# PD_MK2_Connectors.net
KiCad netlist of a schematic drawn in Altium Designer
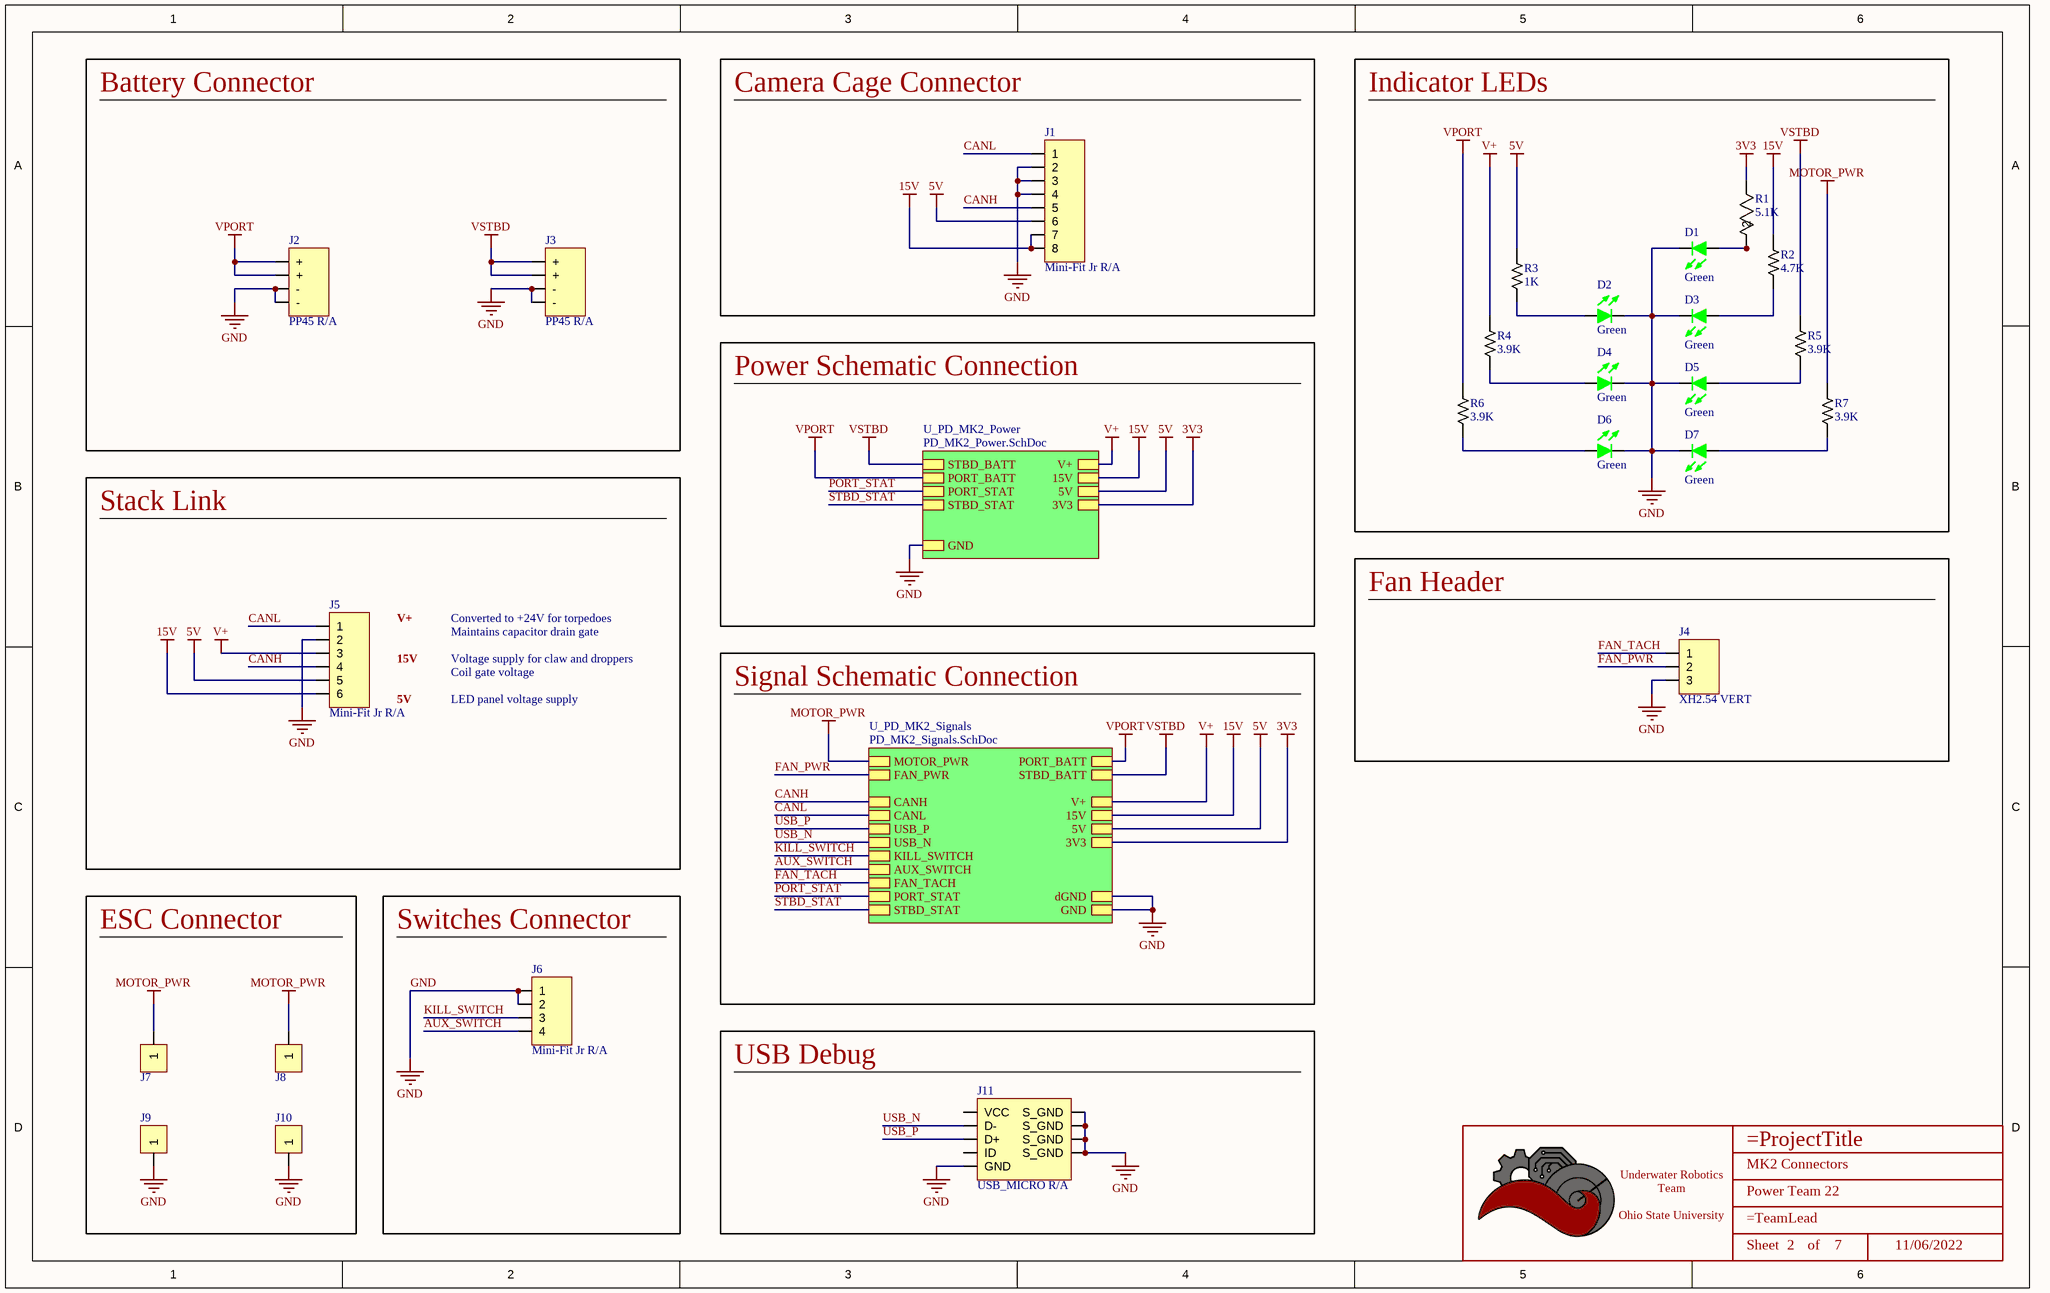
[diagram p0: PD_MK2_Connectors.SchDoc]

(export (version "E")
  (design (tool "Eeschema 10.0.6"))
  (components
    (comp (ref "*")
      (value "Title_Block")
      (footprint "LOGO")
      (description "UWRT Schematic Title Block Template\r\n\r\nCreated June 2021, Dylan Trainor")
      (libsource (lib "UWRT") (part "Title_Block"))
    )
    (comp (ref "D1")
      (value "IN-S63AT5G")
      (footprint "LED_0603")
      (description "LED Green Vf= 3V If = 0.005A\r\nIN-S63AT5G")
      (fields (field (name "COLOR") "Green") (field (name "MADE BY") "Robert Pafford"))
      (libsource (lib "Diodes") (part "LED_Green_0603_3V"))
    )
    (comp (ref "D2")
      (value "IN-S63AT5G")
      (footprint "LED_0603")
      (description "LED Green Vf= 3V If = 0.005A\r\nIN-S63AT5G")
      (fields (field (name "COLOR") "Green") (field (name "MADE BY") "Robert Pafford"))
      (libsource (lib "Diodes") (part "LED_Green_0603_3V"))
    )
    (comp (ref "D3")
      (value "IN-S63AT5G")
      (footprint "LED_0603")
      (description "LED Green Vf= 3V If = 0.005A\r\nIN-S63AT5G")
      (fields (field (name "COLOR") "Green") (field (name "MADE BY") "Robert Pafford"))
      (libsource (lib "Diodes") (part "LED_Green_0603_3V"))
    )
    (comp (ref "D4")
      (value "IN-S63AT5G")
      (footprint "LED_0603")
      (description "LED Green Vf= 3V If = 0.005A\r\nIN-S63AT5G")
      (fields (field (name "COLOR") "Green") (field (name "MADE BY") "Robert Pafford"))
      (libsource (lib "Diodes") (part "LED_Green_0603_3V"))
    )
    (comp (ref "D5")
      (value "IN-S63AT5G")
      (footprint "LED_0603")
      (description "LED Green Vf= 3V If = 0.005A\r\nIN-S63AT5G")
      (fields (field (name "COLOR") "Green") (field (name "MADE BY") "Robert Pafford"))
      (libsource (lib "Diodes") (part "LED_Green_0603_3V"))
    )
    (comp (ref "D6")
      (value "IN-S63AT5G")
      (footprint "LED_0603")
      (description "LED Green Vf= 3V If = 0.005A\r\nIN-S63AT5G")
      (fields (field (name "COLOR") "Green") (field (name "MADE BY") "Robert Pafford"))
      (libsource (lib "Diodes") (part "LED_Green_0603_3V"))
    )
    (comp (ref "D7")
      (value "IN-S63AT5G")
      (footprint "LED_0603")
      (description "LED Green Vf= 3V If = 0.005A\r\nIN-S63AT5G")
      (fields (field (name "COLOR") "Green") (field (name "MADE BY") "Robert Pafford"))
      (libsource (lib "Diodes") (part "LED_Green_0603_3V"))
    )
    (comp (ref "J1")
      (value "Mini-Fit Jr R/A")
      (footprint "CONN_MOLEX_MINIFIT JR_8 POS_R/A")
      (description "Molex Minifit Jr. 5569 \r\n8 Pos R/A Natural")
      (fields (field (name "MANUFACTURER") "Molex") (field (name "CREATED BY") "Flip B"))
      (libsource (lib "Connectors") (part "CONN_MOLEX_MINIFIT JR_8POS_R/A"))
    )
    (comp (ref "J2")
      (value "PP45 R/A")
      (footprint "CONN_ANDERSON_PP45_4 POS_R/A")
      (description "Anderson PP45\r\n4 Pos R/A Red/Black")
      (fields (field (name "MANUFACTURER") "Anderson") (field (name "CREATED BY") "Flip B"))
      (libsource (lib "Connectors") (part "CONN_ANDERSON_2x2_R/A"))
    )
    (comp (ref "J3")
      (value "PP45 R/A")
      (footprint "CONN_ANDERSON_PP45_4 POS_R/A")
      (description "Anderson PP45\r\n4 Pos R/A Red/Black")
      (fields (field (name "MANUFACTURER") "Anderson") (field (name "CREATED BY") "Flip B"))
      (libsource (lib "Connectors") (part "CONN_ANDERSON_2x2_R/A"))
    )
    (comp (ref "J4")
      (value "XH2.54 VERT")
      (footprint "CONN_JST_XH254_3POS_VERT")
      (description "JST XH 2.54mm Pitch 3 Pos Vertical")
      (fields (field (name "MANUFACTURER") "JST") (field (name "CREATED BY") "Robert P"))
      (libsource (lib "Connectors") (part "CONN_JST_XH254_3POS_VERT"))
    )
    (comp (ref "J5")
      (value "Mini-Fit Jr R/A")
      (footprint "CONN_MOLEX_MINIFIT JR_6 POS_R/A")
      (description "Molex Minifit Jr. 5569 \r\n6 Pos R/A Natural")
      (fields (field (name "MANUFACTURER") "Molex") (field (name "CREATED BY") "Flip B"))
      (libsource (lib "Connectors") (part "CONN_MOLEX_MINIFIT JR_6POS_R/A"))
    )
    (comp (ref "J6")
      (value "Mini-Fit Jr R/A")
      (footprint "CONN_MOLEX_MINIFIT JR_4 POS_R/A")
      (description "Molex Minifit Jr. 5569 \r\n4 Pos R/A Natural")
      (fields (field (name "MANUFACTURER") "Molex") (field (name "CREATED BY") "Flip B"))
      (libsource (lib "Connectors") (part "CONN_MOLEX_MINIFIT JR_4POS_R/A"))
    )
    (comp (ref "J7")
      (value "Redcube M4 Term 85A")
      (footprint "Redcube M4 Term 85A")
      (fields (field (name "CREATED BY") "Nahtan Ayer"))
      (libsource (lib "") (part "Redcube M4 Term 85A_1"))
    )
    (comp (ref "J8")
      (value "Redcube M4 Term 85A")
      (footprint "Redcube M4 Term 85A")
      (fields (field (name "CREATED BY") "Nahtan Ayer"))
      (libsource (lib "") (part "Redcube M4 Term 85A_1"))
    )
    (comp (ref "J9")
      (value "Redcube M4 Term 85A")
      (footprint "Redcube M4 Term 85A")
      (fields (field (name "CREATED BY") "Nahtan Ayer"))
      (libsource (lib "Connectors") (part "Redcube M4 Term 85A"))
    )
    (comp (ref "J10")
      (value "Redcube M4 Term 85A")
      (footprint "Redcube M4 Term 85A")
      (fields (field (name "CREATED BY") "Nahtan Ayer"))
      (libsource (lib "Connectors") (part "Redcube M4 Term 85A"))
    )
    (comp (ref "J11")
      (value "USB_MICRO R/A")
      (footprint "CONN_MINIUSB")
      (description "Amphenol Micro USB-B\r\nUSB2.0 5 Pin Right Angle SMD")
      (fields (field (name "MANUFACTURER") "Amphenol") (field (name "CREATED BY") "Flip B"))
      (libsource (lib "Connectors") (part "CONN_MICROUSB"))
    )
    (comp (ref "R1")
      (value "5.1K")
      (footprint "RC0603N_PAN")
      (description "5.1 kOhms ±0.1% 0.1W, 1/10W Chip Resistor 0603 (1608 Metric) Automotive AEC-Q200 Thin Film")
      (fields
        (field (name "MANUFACTURER_PART_NUMBER") "ERA-3AEB512V_2")
        (field (name "COPYRIGHT") "Copyright (C) 2023 Ultra Librarian. All rights reserved.")
      )
      (libsource (lib "Resistors") (part "ERA-3AEB512V_2"))
    )
    (comp (ref "R2")
      (value "4.7k Ohm 5% 1/10W")
      (footprint "RESISTOR_0603")
      (description "RES 4.7k OHM 5% 1/10W 0603")
      (fields
        (field (name "TOLERANCE") "+/- 5%")
        (field (name "VALUE  (OHMS)") "4.7K")
        (field (name "MADE BY") "Robert Pafford")
      )
      (libsource (lib "Resistors") (part "RESISTOR_4.7K_0603"))
    )
    (comp (ref "R3")
      (value "1k Ohm 5% 1/8W")
      (footprint "RESISTOR_0603")
      (description "RES 1k OHM 5% 1/8W 0603")
      (fields
        (field (name "TOLERANCE") "+/- 5%")
        (field (name "VALUE  (OHMS)") "1K")
        (field (name "MADE BY") "Robert Pafford")
      )
      (libsource (lib "Resistors") (part "RESISTOR_1K_0603"))
    )
    (comp (ref "R4")
      (value "3.9k Ohm 5% 1/10W")
      (footprint "RESISTOR_0603")
      (description "RES 3.9k OHM 1% 1/10W 0603")
      (fields
        (field (name "TOLERANCE") "+/- 1%")
        (field (name "VALUE  (OHMS)") "3.9K")
        (field (name "MADE BY") "Robert Pafford")
      )
      (libsource (lib "Resistors") (part "RESISTOR_3.9K_0603"))
    )
    (comp (ref "R5")
      (value "3.9k Ohm 5% 1/10W")
      (footprint "RESISTOR_0603")
      (description "RES 3.9k OHM 1% 1/10W 0603")
      (fields
        (field (name "TOLERANCE") "+/- 1%")
        (field (name "VALUE  (OHMS)") "3.9K")
        (field (name "MADE BY") "Robert Pafford")
      )
      (libsource (lib "Resistors") (part "RESISTOR_3.9K_0603"))
    )
    (comp (ref "R6")
      (value "3.9k Ohm 5% 1/10W")
      (footprint "RESISTOR_0603")
      (description "RES 3.9k OHM 1% 1/10W 0603")
      (fields
        (field (name "TOLERANCE") "+/- 1%")
        (field (name "VALUE  (OHMS)") "3.9K")
        (field (name "MADE BY") "Robert Pafford")
      )
      (libsource (lib "Resistors") (part "RESISTOR_3.9K_0603"))
    )
    (comp (ref "R7")
      (value "3.9k Ohm 5% 1/10W")
      (footprint "RESISTOR_0603")
      (description "RES 3.9k OHM 1% 1/10W 0603")
      (fields
        (field (name "TOLERANCE") "+/- 1%")
        (field (name "VALUE  (OHMS)") "3.9K")
        (field (name "MADE BY") "Robert Pafford")
      )
      (libsource (lib "Resistors") (part "RESISTOR_3.9K_0603"))
    )
  )
  (nets
    (net (code "1") (name "/AUX_SWITCH") (class "Default")
      (node (ref "J6") (pin "4") (pinfunction "4_4") (pintype "passive"))
    )
    (net (code "2") (name "/CANH") (class "Default")
      (node (ref "J1") (pin "5") (pinfunction "5_5") (pintype "passive"))
      (node (ref "J5") (pin "4") (pinfunction "4_4") (pintype "passive"))
    )
    (net (code "3") (name "/CANL") (class "Default")
      (node (ref "J1") (pin "1") (pinfunction "1_1") (pintype "passive"))
      (node (ref "J5") (pin "1") (pinfunction "1_1") (pintype "passive"))
    )
    (net (code "4") (name "/FAN_PWR") (class "Default")
      (node (ref "J4") (pin "2") (pinfunction "2_2") (pintype "passive"))
    )
    (net (code "5") (name "/FAN_TACH") (class "Default")
      (node (ref "J4") (pin "1") (pinfunction "1_1") (pintype "passive"))
    )
    (net (code "6") (name "/KILL_SWITCH") (class "Default")
      (node (ref "J6") (pin "3") (pinfunction "3_3") (pintype "passive"))
    )
    (net (code "9") (name "/USB_N") (class "Default")
      (node (ref "J11") (pin "2") (pinfunction "D-_2") (pintype "passive"))
    )
    (net (code "10") (name "/USB_P") (class "Default")
      (node (ref "J11") (pin "3") (pinfunction "D+_3") (pintype "passive"))
    )
    (net (code "11") (name "3V3") (class "Default")
      (node (ref "R1") (pin "1") (pinfunction "1_1") (pintype "passive"))
    )
    (net (code "12") (name "5V") (class "Default")
      (node (ref "J1") (pin "6") (pinfunction "6_6") (pintype "passive"))
      (node (ref "J5") (pin "5") (pinfunction "5_5") (pintype "passive"))
      (node (ref "R3") (pin "1") (pinfunction "1_1") (pintype "passive"))
    )
    (net (code "13") (name "15V") (class "Default")
      (node (ref "J1") (pin "7") (pinfunction "7_7") (pintype "passive"))
      (node (ref "J1") (pin "8") (pinfunction "8_8") (pintype "passive"))
      (node (ref "J5") (pin "6") (pinfunction "6_6") (pintype "passive"))
      (node (ref "R2") (pin "1") (pinfunction "1_1") (pintype "passive"))
    )
    (net (code "14") (name "GND") (class "Default")
      (node (ref "D1") (pin "2") (pinfunction "2_2") (pintype "passive"))
      (node (ref "D2") (pin "2") (pinfunction "2_2") (pintype "passive"))
      (node (ref "D3") (pin "2") (pinfunction "2_2") (pintype "passive"))
      (node (ref "D4") (pin "2") (pinfunction "2_2") (pintype "passive"))
      (node (ref "D5") (pin "2") (pinfunction "2_2") (pintype "passive"))
      (node (ref "D6") (pin "2") (pinfunction "2_2") (pintype "passive"))
      (node (ref "D7") (pin "2") (pinfunction "2_2") (pintype "passive"))
      (node (ref "J1") (pin "2") (pinfunction "2_2") (pintype "passive"))
      (node (ref "J1") (pin "3") (pinfunction "3_3") (pintype "passive"))
      (node (ref "J1") (pin "4") (pinfunction "4_4") (pintype "passive"))
      (node (ref "J10") (pin "1") (pinfunction "1_1") (pintype "passive"))
      (node (ref "J11") (pin "5") (pinfunction "GND_5") (pintype "passive"))
      (node (ref "J11") (pin "6") (pinfunction "S_GND_6") (pintype "passive"))
      (node (ref "J11") (pin "7") (pinfunction "S_GND_7") (pintype "passive"))
      (node (ref "J11") (pin "8") (pinfunction "S_GND_8") (pintype "passive"))
      (node (ref "J11") (pin "9") (pinfunction "S_GND_9") (pintype "passive"))
      (node (ref "J2") (pin "3") (pinfunction "-_3") (pintype "passive"))
      (node (ref "J2") (pin "4") (pinfunction "-_4") (pintype "passive"))
      (node (ref "J3") (pin "3") (pinfunction "-_3") (pintype "passive"))
      (node (ref "J3") (pin "4") (pinfunction "-_4") (pintype "passive"))
      (node (ref "J4") (pin "3") (pinfunction "3_3") (pintype "passive"))
      (node (ref "J5") (pin "2") (pinfunction "2_2") (pintype "passive"))
      (node (ref "J6") (pin "1") (pinfunction "1_1") (pintype "passive"))
      (node (ref "J6") (pin "2") (pinfunction "2_2") (pintype "passive"))
      (node (ref "J9") (pin "1") (pinfunction "1_1") (pintype "passive"))
    )
    (net (code "15") (name "MOTOR_PWR") (class "Default")
      (node (ref "J7") (pin "1") (pinfunction "1_1") (pintype "passive"))
      (node (ref "J8") (pin "1") (pinfunction "1_1") (pintype "passive"))
      (node (ref "R7") (pin "1") (pinfunction "1_1") (pintype "passive"))
    )
    (net (code "16") (name "Net-(D1-Pad1)") (class "Default")
      (node (ref "D1") (pin "1") (pinfunction "1_1") (pintype "passive"))
      (node (ref "R1") (pin "2") (pinfunction "2_2") (pintype "passive"))
    )
    (net (code "17") (name "Net-(D2-Pad1)") (class "Default")
      (node (ref "D2") (pin "1") (pinfunction "1_1") (pintype "passive"))
      (node (ref "R3") (pin "2") (pinfunction "2_2") (pintype "passive"))
    )
    (net (code "18") (name "Net-(D3-Pad1)") (class "Default")
      (node (ref "D3") (pin "1") (pinfunction "1_1") (pintype "passive"))
      (node (ref "R2") (pin "2") (pinfunction "2_2") (pintype "passive"))
    )
    (net (code "19") (name "Net-(D4-Pad1)") (class "Default")
      (node (ref "D4") (pin "1") (pinfunction "1_1") (pintype "passive"))
      (node (ref "R4") (pin "2") (pinfunction "2_2") (pintype "passive"))
    )
    (net (code "20") (name "Net-(D5-Pad1)") (class "Default")
      (node (ref "D5") (pin "1") (pinfunction "1_1") (pintype "passive"))
      (node (ref "R5") (pin "2") (pinfunction "2_2") (pintype "passive"))
    )
    (net (code "21") (name "Net-(D6-Pad1)") (class "Default")
      (node (ref "D6") (pin "1") (pinfunction "1_1") (pintype "passive"))
      (node (ref "R6") (pin "2") (pinfunction "2_2") (pintype "passive"))
    )
    (net (code "22") (name "Net-(D7-Pad1)") (class "Default")
      (node (ref "D7") (pin "1") (pinfunction "1_1") (pintype "passive"))
      (node (ref "R7") (pin "2") (pinfunction "2_2") (pintype "passive"))
    )
    (net (code "23") (name "V+") (class "Default")
      (node (ref "J5") (pin "3") (pinfunction "3_3") (pintype "passive"))
      (node (ref "R4") (pin "1") (pinfunction "1_1") (pintype "passive"))
    )
    (net (code "24") (name "VPORT") (class "Default")
      (node (ref "J2") (pin "1") (pinfunction "+_1") (pintype "passive"))
      (node (ref "J2") (pin "2") (pinfunction "+_2") (pintype "passive"))
      (node (ref "R6") (pin "1") (pinfunction "1_1") (pintype "passive"))
    )
    (net (code "25") (name "VSTBD") (class "Default")
      (node (ref "J3") (pin "1") (pinfunction "+_1") (pintype "passive"))
      (node (ref "J3") (pin "2") (pinfunction "+_2") (pintype "passive"))
      (node (ref "R5") (pin "1") (pinfunction "1_1") (pintype "passive"))
    )
    (net (code "26") (name "unconnected-(J11-ID-Pad4)") (class "Default")
      (node (ref "J11") (pin "4") (pinfunction "ID_4") (pintype "passive"))
    )
    (net (code "27") (name "unconnected-(J11-VCC-Pad1)") (class "Default")
      (node (ref "J11") (pin "1") (pinfunction "VCC_1") (pintype "passive"))
    )
  )
)
